# Cpcis_connectors_P1_P2_P3.net
KiCad netlist of a schematic drawn in Altium Designer
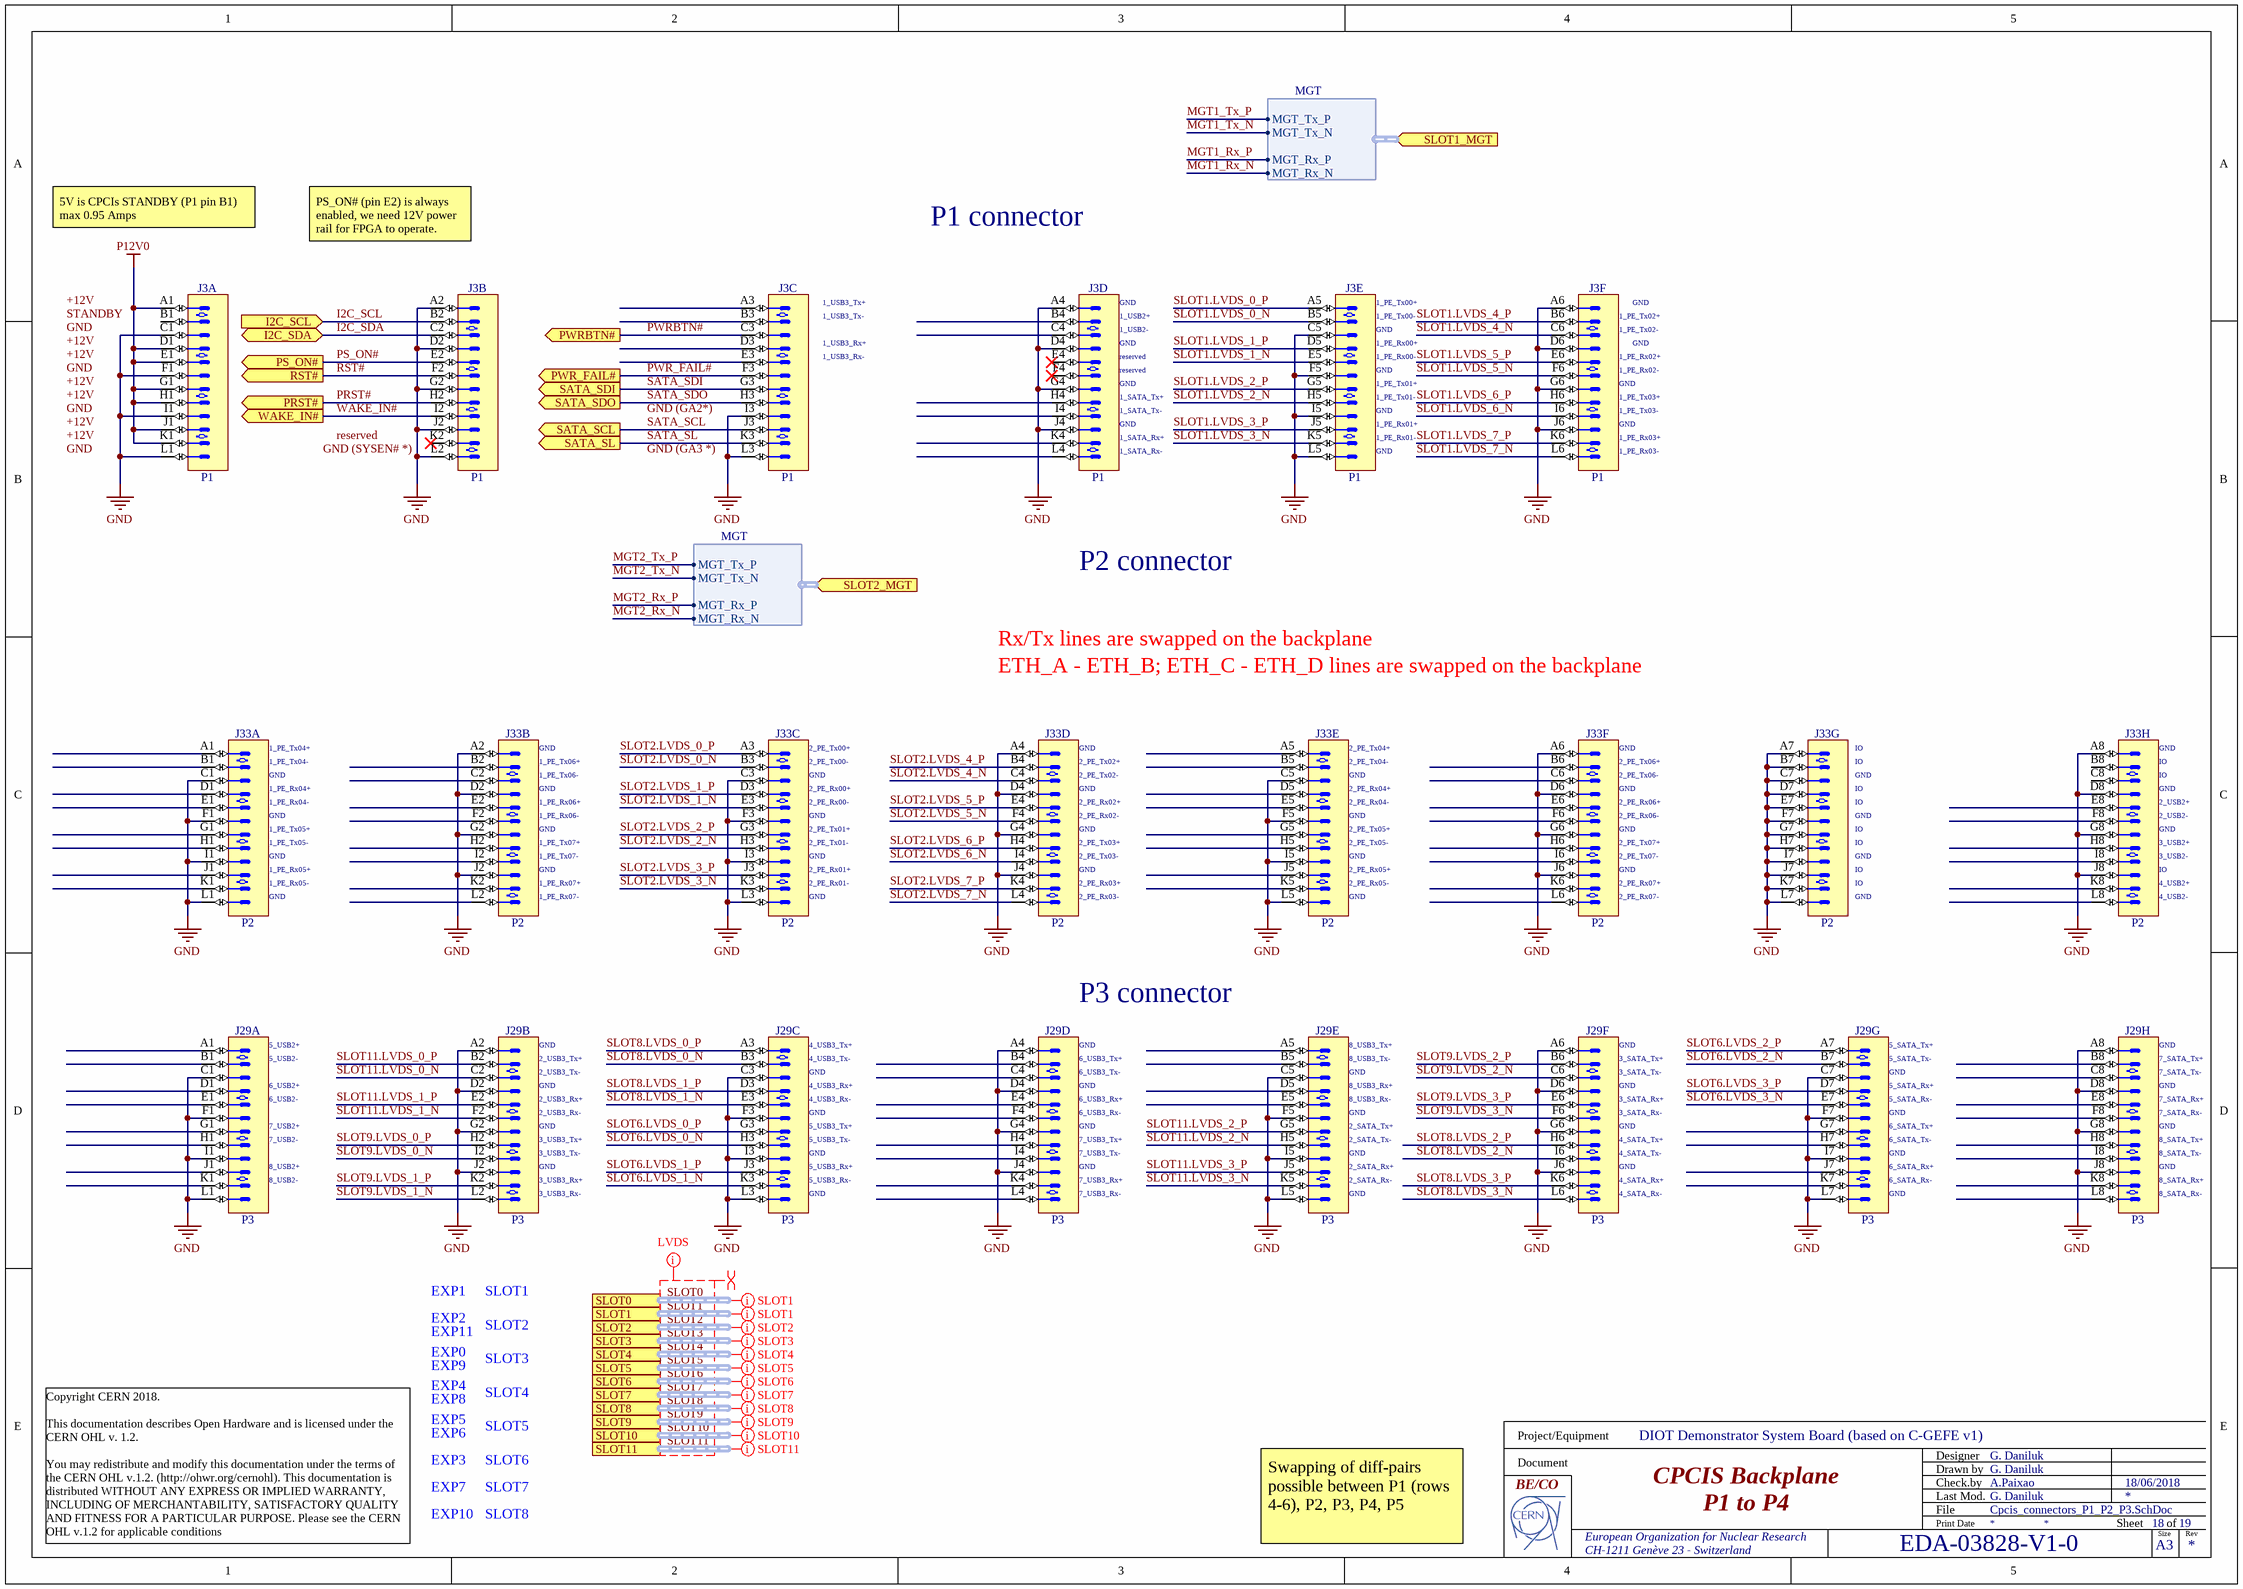
[diagram p0: Cpcis_connectors_P1_P2_P3.SchDoc]

(export (version "E")
  (design (tool "Eeschema 10.0.6"))
  (components
    (comp (ref "J3")
      (value "P1")
      (footprint "AMPHENOL_10052825-101LF")
      (description "72 Contacts Header, 6 Columns, 4 Pairs per Column")
      (fields
        (field (name "PART NUMBER") "AMPHENOL_10052825-101LF")
        (field (name "MANUFACTURER") "AMPHENOL")
        (field (name "AUTHOR") "CERN DEM MR")
      )
      (libsource (lib "Connectors") (part "AMPHENOL_10052825-101LF"))
    )
    (comp (ref "J29")
      (value "P3")
      (footprint "AMPHENOL_10052837-101LF")
      (description "96 Contacts Header, 8 Columns, 4 Pairs per Column")
      (fields
        (field (name "PART NUMBER") "AMPHENOL_10052837-101LF")
        (field (name "MANUFACTURER") "AMPHENOL")
        (field (name "AUTHOR") "CERN DEM MR")
      )
      (libsource (lib "Connectors") (part "AMPHENOL_10052837-101LF"))
    )
    (comp (ref "J33")
      (value "P2")
      (footprint "AMPHENOL_10052837-101LF")
      (description "96 Contacts Header, 8 Columns, 4 Pairs per Column")
      (fields
        (field (name "PART NUMBER") "AMPHENOL_10052837-101LF")
        (field (name "MANUFACTURER") "AMPHENOL")
        (field (name "AUTHOR") "CERN DEM MR")
      )
      (libsource (lib "Connectors") (part "AMPHENOL_10052837-101LF"))
    )
  )
  (nets
    (net (code "18") (name "/I2C_SCL") (class "Default")
      (node (ref "J3") (pin "B2") (pinfunction "B2_B2") (pintype "bidirectional"))
    )
    (net (code "19") (name "/I2C_SDA") (class "Default")
      (node (ref "J3") (pin "C2") (pinfunction "C2_C2") (pintype "bidirectional"))
    )
    (net (code "28") (name "/PRST#") (class "Default")
      (node (ref "J3") (pin "H2") (pinfunction "H2_H2") (pintype "bidirectional"))
    )
    (net (code "29") (name "/PS_ON#") (class "Default")
      (node (ref "J3") (pin "E2") (pinfunction "E2_E2") (pintype "bidirectional"))
    )
    (net (code "30") (name "/PWRBTN#") (class "Default")
      (node (ref "J3") (pin "C3") (pinfunction "C3_C3") (pintype "bidirectional"))
    )
    (net (code "31") (name "/PWR_FAIL#") (class "Default")
      (node (ref "J3") (pin "F3") (pinfunction "F3_F3") (pintype "bidirectional"))
    )
    (net (code "32") (name "/RST#") (class "Default")
      (node (ref "J3") (pin "F2") (pinfunction "F2_F2") (pintype "bidirectional"))
    )
    (net (code "33") (name "/SATA_SCL") (class "Default")
      (node (ref "J3") (pin "J3") (pinfunction "J3_J3") (pintype "bidirectional"))
    )
    (net (code "34") (name "/SATA_SDI") (class "Default")
      (node (ref "J3") (pin "G3") (pinfunction "G3_G3") (pintype "bidirectional"))
    )
    (net (code "35") (name "/SATA_SDO") (class "Default")
      (node (ref "J3") (pin "H3") (pinfunction "H3_H3") (pintype "bidirectional"))
    )
    (net (code "36") (name "/SATA_SL") (class "Default")
      (node (ref "J3") (pin "K3") (pinfunction "K3_K3") (pintype "bidirectional"))
    )
    (net (code "37") (name "/SLOT1.LVDS_0_N") (class "Default")
      (node (ref "J3") (pin "B5") (pinfunction "B5_B5") (pintype "bidirectional"))
    )
    (net (code "38") (name "/SLOT1.LVDS_0_P") (class "Default")
      (node (ref "J3") (pin "A5") (pinfunction "A5_A5") (pintype "bidirectional"))
    )
    (net (code "39") (name "/SLOT1.LVDS_1_N") (class "Default")
      (node (ref "J3") (pin "E5") (pinfunction "E5_E5") (pintype "bidirectional"))
    )
    (net (code "40") (name "/SLOT1.LVDS_1_P") (class "Default")
      (node (ref "J3") (pin "D5") (pinfunction "D5_D5") (pintype "bidirectional"))
    )
    (net (code "41") (name "/SLOT1.LVDS_2_N") (class "Default")
      (node (ref "J3") (pin "H5") (pinfunction "H5_H5") (pintype "bidirectional"))
    )
    (net (code "42") (name "/SLOT1.LVDS_2_P") (class "Default")
      (node (ref "J3") (pin "G5") (pinfunction "G5_G5") (pintype "bidirectional"))
    )
    (net (code "43") (name "/SLOT1.LVDS_3_N") (class "Default")
      (node (ref "J3") (pin "K5") (pinfunction "K5_K5") (pintype "bidirectional"))
    )
    (net (code "44") (name "/SLOT1.LVDS_3_P") (class "Default")
      (node (ref "J3") (pin "J5") (pinfunction "J5_J5") (pintype "bidirectional"))
    )
    (net (code "45") (name "/SLOT1.LVDS_4_N") (class "Default")
      (node (ref "J3") (pin "C6") (pinfunction "C6_C6") (pintype "bidirectional"))
    )
    (net (code "46") (name "/SLOT1.LVDS_4_P") (class "Default")
      (node (ref "J3") (pin "B6") (pinfunction "B6_B6") (pintype "bidirectional"))
    )
    (net (code "47") (name "/SLOT1.LVDS_5_N") (class "Default")
      (node (ref "J3") (pin "F6") (pinfunction "F6_F6") (pintype "bidirectional"))
    )
    (net (code "48") (name "/SLOT1.LVDS_5_P") (class "Default")
      (node (ref "J3") (pin "E6") (pinfunction "E6_E6") (pintype "bidirectional"))
    )
    (net (code "49") (name "/SLOT1.LVDS_6_N") (class "Default")
      (node (ref "J3") (pin "I6") (pinfunction "I6_I6") (pintype "bidirectional"))
    )
    (net (code "50") (name "/SLOT1.LVDS_6_P") (class "Default")
      (node (ref "J3") (pin "H6") (pinfunction "H6_H6") (pintype "bidirectional"))
    )
    (net (code "51") (name "/SLOT1.LVDS_7_N") (class "Default")
      (node (ref "J3") (pin "L6") (pinfunction "L6_L6") (pintype "bidirectional"))
    )
    (net (code "52") (name "/SLOT1.LVDS_7_P") (class "Default")
      (node (ref "J3") (pin "K6") (pinfunction "K6_K6") (pintype "bidirectional"))
    )
    (net (code "53") (name "/SLOT2.LVDS_0_N") (class "Default")
      (node (ref "J33") (pin "B3") (pinfunction "B3_B3") (pintype "bidirectional"))
    )
    (net (code "54") (name "/SLOT2.LVDS_0_P") (class "Default")
      (node (ref "J33") (pin "A3") (pinfunction "A3_A3") (pintype "bidirectional"))
    )
    (net (code "55") (name "/SLOT2.LVDS_1_N") (class "Default")
      (node (ref "J33") (pin "E3") (pinfunction "E3_E3") (pintype "bidirectional"))
    )
    (net (code "56") (name "/SLOT2.LVDS_1_P") (class "Default")
      (node (ref "J33") (pin "D3") (pinfunction "D3_D3") (pintype "bidirectional"))
    )
    (net (code "57") (name "/SLOT2.LVDS_2_N") (class "Default")
      (node (ref "J33") (pin "H3") (pinfunction "H3_H3") (pintype "bidirectional"))
    )
    (net (code "58") (name "/SLOT2.LVDS_2_P") (class "Default")
      (node (ref "J33") (pin "G3") (pinfunction "G3_G3") (pintype "bidirectional"))
    )
    (net (code "59") (name "/SLOT2.LVDS_3_N") (class "Default")
      (node (ref "J33") (pin "K3") (pinfunction "K3_K3") (pintype "bidirectional"))
    )
    (net (code "60") (name "/SLOT2.LVDS_3_P") (class "Default")
      (node (ref "J33") (pin "J3") (pinfunction "J3_J3") (pintype "bidirectional"))
    )
    (net (code "61") (name "/SLOT2.LVDS_4_N") (class "Default")
      (node (ref "J33") (pin "C4") (pinfunction "C4_C4") (pintype "bidirectional"))
    )
    (net (code "62") (name "/SLOT2.LVDS_4_P") (class "Default")
      (node (ref "J33") (pin "B4") (pinfunction "B4_B4") (pintype "bidirectional"))
    )
    (net (code "63") (name "/SLOT2.LVDS_5_N") (class "Default")
      (node (ref "J33") (pin "F4") (pinfunction "F4_F4") (pintype "bidirectional"))
    )
    (net (code "64") (name "/SLOT2.LVDS_5_P") (class "Default")
      (node (ref "J33") (pin "E4") (pinfunction "E4_E4") (pintype "bidirectional"))
    )
    (net (code "65") (name "/SLOT2.LVDS_6_N") (class "Default")
      (node (ref "J33") (pin "I4") (pinfunction "I4_I4") (pintype "bidirectional"))
    )
    (net (code "66") (name "/SLOT2.LVDS_6_P") (class "Default")
      (node (ref "J33") (pin "H4") (pinfunction "H4_H4") (pintype "bidirectional"))
    )
    (net (code "67") (name "/SLOT2.LVDS_7_N") (class "Default")
      (node (ref "J33") (pin "L4") (pinfunction "L4_L4") (pintype "bidirectional"))
    )
    (net (code "68") (name "/SLOT2.LVDS_7_P") (class "Default")
      (node (ref "J33") (pin "K4") (pinfunction "K4_K4") (pintype "bidirectional"))
    )
    (net (code "69") (name "/SLOT6.LVDS_0_N") (class "Default")
      (node (ref "J29") (pin "H3") (pinfunction "H3_H3") (pintype "bidirectional"))
    )
    (net (code "70") (name "/SLOT6.LVDS_0_P") (class "Default")
      (node (ref "J29") (pin "G3") (pinfunction "G3_G3") (pintype "bidirectional"))
    )
    (net (code "71") (name "/SLOT6.LVDS_1_N") (class "Default")
      (node (ref "J29") (pin "K3") (pinfunction "K3_K3") (pintype "bidirectional"))
    )
    (net (code "72") (name "/SLOT6.LVDS_1_P") (class "Default")
      (node (ref "J29") (pin "J3") (pinfunction "J3_J3") (pintype "bidirectional"))
    )
    (net (code "73") (name "/SLOT6.LVDS_2_N") (class "Default")
      (node (ref "J29") (pin "B7") (pinfunction "B7_B7") (pintype "bidirectional"))
    )
    (net (code "74") (name "/SLOT6.LVDS_2_P") (class "Default")
      (node (ref "J29") (pin "A7") (pinfunction "A7_A7") (pintype "bidirectional"))
    )
    (net (code "75") (name "/SLOT6.LVDS_3_N") (class "Default")
      (node (ref "J29") (pin "E7") (pinfunction "E7_E7") (pintype "bidirectional"))
    )
    (net (code "76") (name "/SLOT6.LVDS_3_P") (class "Default")
      (node (ref "J29") (pin "D7") (pinfunction "D7_D7") (pintype "bidirectional"))
    )
    (net (code "77") (name "/SLOT8.LVDS_0_N") (class "Default")
      (node (ref "J29") (pin "B3") (pinfunction "B3_B3") (pintype "bidirectional"))
    )
    (net (code "78") (name "/SLOT8.LVDS_0_P") (class "Default")
      (node (ref "J29") (pin "A3") (pinfunction "A3_A3") (pintype "bidirectional"))
    )
    (net (code "79") (name "/SLOT8.LVDS_1_N") (class "Default")
      (node (ref "J29") (pin "E3") (pinfunction "E3_E3") (pintype "bidirectional"))
    )
    (net (code "80") (name "/SLOT8.LVDS_1_P") (class "Default")
      (node (ref "J29") (pin "D3") (pinfunction "D3_D3") (pintype "bidirectional"))
    )
    (net (code "81") (name "/SLOT8.LVDS_2_N") (class "Default")
      (node (ref "J29") (pin "I6") (pinfunction "I6_I6") (pintype "bidirectional"))
    )
    (net (code "82") (name "/SLOT8.LVDS_2_P") (class "Default")
      (node (ref "J29") (pin "H6") (pinfunction "H6_H6") (pintype "bidirectional"))
    )
    (net (code "83") (name "/SLOT8.LVDS_3_N") (class "Default")
      (node (ref "J29") (pin "L6") (pinfunction "L6_L6") (pintype "bidirectional"))
    )
    (net (code "84") (name "/SLOT8.LVDS_3_P") (class "Default")
      (node (ref "J29") (pin "K6") (pinfunction "K6_K6") (pintype "bidirectional"))
    )
    (net (code "85") (name "/SLOT9.LVDS_0_N") (class "Default")
      (node (ref "J29") (pin "I2") (pinfunction "I2_I2") (pintype "bidirectional"))
    )
    (net (code "86") (name "/SLOT9.LVDS_0_P") (class "Default")
      (node (ref "J29") (pin "H2") (pinfunction "H2_H2") (pintype "bidirectional"))
    )
    (net (code "87") (name "/SLOT9.LVDS_1_N") (class "Default")
      (node (ref "J29") (pin "L2") (pinfunction "L2_L2") (pintype "bidirectional"))
    )
    (net (code "88") (name "/SLOT9.LVDS_1_P") (class "Default")
      (node (ref "J29") (pin "K2") (pinfunction "K2_K2") (pintype "bidirectional"))
    )
    (net (code "89") (name "/SLOT9.LVDS_2_N") (class "Default")
      (node (ref "J29") (pin "C6") (pinfunction "C6_C6") (pintype "bidirectional"))
    )
    (net (code "90") (name "/SLOT9.LVDS_2_P") (class "Default")
      (node (ref "J29") (pin "B6") (pinfunction "B6_B6") (pintype "bidirectional"))
    )
    (net (code "91") (name "/SLOT9.LVDS_3_N") (class "Default")
      (node (ref "J29") (pin "F6") (pinfunction "F6_F6") (pintype "bidirectional"))
    )
    (net (code "92") (name "/SLOT9.LVDS_3_P") (class "Default")
      (node (ref "J29") (pin "E6") (pinfunction "E6_E6") (pintype "bidirectional"))
    )
    (net (code "93") (name "/SLOT11.LVDS_0_N") (class "Default")
      (node (ref "J29") (pin "C2") (pinfunction "C2_C2") (pintype "bidirectional"))
    )
    (net (code "94") (name "/SLOT11.LVDS_0_P") (class "Default")
      (node (ref "J29") (pin "B2") (pinfunction "B2_B2") (pintype "bidirectional"))
    )
    (net (code "95") (name "/SLOT11.LVDS_1_N") (class "Default")
      (node (ref "J29") (pin "F2") (pinfunction "F2_F2") (pintype "bidirectional"))
    )
    (net (code "96") (name "/SLOT11.LVDS_1_P") (class "Default")
      (node (ref "J29") (pin "E2") (pinfunction "E2_E2") (pintype "bidirectional"))
    )
    (net (code "97") (name "/SLOT11.LVDS_2_N") (class "Default")
      (node (ref "J29") (pin "H5") (pinfunction "H5_H5") (pintype "bidirectional"))
    )
    (net (code "98") (name "/SLOT11.LVDS_2_P") (class "Default")
      (node (ref "J29") (pin "G5") (pinfunction "G5_G5") (pintype "bidirectional"))
    )
    (net (code "99") (name "/SLOT11.LVDS_3_N") (class "Default")
      (node (ref "J29") (pin "K5") (pinfunction "K5_K5") (pintype "bidirectional"))
    )
    (net (code "100") (name "/SLOT11.LVDS_3_P") (class "Default")
      (node (ref "J29") (pin "J5") (pinfunction "J5_J5") (pintype "bidirectional"))
    )
    (net (code "102") (name "/WAKE_IN#") (class "Default")
      (node (ref "J3") (pin "I2") (pinfunction "I2_I2") (pintype "bidirectional"))
    )
    (net (code "117") (name "GND") (class "Default")
      (node (ref "J29") (pin "A2") (pinfunction "A2_A2") (pintype "bidirectional"))
      (node (ref "J29") (pin "A4") (pinfunction "A4_A4") (pintype "bidirectional"))
      (node (ref "J29") (pin "A6") (pinfunction "A6_A6") (pintype "bidirectional"))
      (node (ref "J29") (pin "A8") (pinfunction "A8_A8") (pintype "bidirectional"))
      (node (ref "J29") (pin "C1") (pinfunction "C1_C1") (pintype "bidirectional"))
      (node (ref "J29") (pin "C3") (pinfunction "C3_C3") (pintype "bidirectional"))
      (node (ref "J29") (pin "C5") (pinfunction "C5_C5") (pintype "bidirectional"))
      (node (ref "J29") (pin "C7") (pinfunction "C7_C7") (pintype "bidirectional"))
      (node (ref "J29") (pin "D2") (pinfunction "D2_D2") (pintype "bidirectional"))
      (node (ref "J29") (pin "D4") (pinfunction "D4_D4") (pintype "bidirectional"))
      (node (ref "J29") (pin "D6") (pinfunction "D6_D6") (pintype "bidirectional"))
      (node (ref "J29") (pin "D8") (pinfunction "D8_D8") (pintype "bidirectional"))
      (node (ref "J29") (pin "F1") (pinfunction "F1_F1") (pintype "bidirectional"))
      (node (ref "J29") (pin "F3") (pinfunction "F3_F3") (pintype "bidirectional"))
      (node (ref "J29") (pin "F5") (pinfunction "F5_F5") (pintype "bidirectional"))
      (node (ref "J29") (pin "F7") (pinfunction "F7_F7") (pintype "bidirectional"))
      (node (ref "J29") (pin "G2") (pinfunction "G2_G2") (pintype "bidirectional"))
      (node (ref "J29") (pin "G4") (pinfunction "G4_G4") (pintype "bidirectional"))
      (node (ref "J29") (pin "G6") (pinfunction "G6_G6") (pintype "bidirectional"))
      (node (ref "J29") (pin "G8") (pinfunction "G8_G8") (pintype "bidirectional"))
      (node (ref "J29") (pin "I1") (pinfunction "I1_I1") (pintype "bidirectional"))
      (node (ref "J29") (pin "I3") (pinfunction "I3_I3") (pintype "bidirectional"))
      (node (ref "J29") (pin "I5") (pinfunction "I5_I5") (pintype "bidirectional"))
      (node (ref "J29") (pin "I7") (pinfunction "I7_I7") (pintype "bidirectional"))
      (node (ref "J29") (pin "J2") (pinfunction "J2_J2") (pintype "bidirectional"))
      (node (ref "J29") (pin "J4") (pinfunction "J4_J4") (pintype "bidirectional"))
      (node (ref "J29") (pin "J6") (pinfunction "J6_J6") (pintype "bidirectional"))
      (node (ref "J29") (pin "J8") (pinfunction "J8_J8") (pintype "bidirectional"))
      (node (ref "J29") (pin "L1") (pinfunction "L1_L1") (pintype "bidirectional"))
      (node (ref "J29") (pin "L3") (pinfunction "L3_L3") (pintype "bidirectional"))
      (node (ref "J29") (pin "L5") (pinfunction "L5_L5") (pintype "bidirectional"))
      (node (ref "J29") (pin "L7") (pinfunction "L7_L7") (pintype "bidirectional"))
      (node (ref "J3") (pin "A2") (pinfunction "A2_A2") (pintype "bidirectional"))
      (node (ref "J3") (pin "A4") (pinfunction "A4_A4") (pintype "bidirectional"))
      (node (ref "J3") (pin "A6") (pinfunction "A6_A6") (pintype "bidirectional"))
      (node (ref "J3") (pin "C1") (pinfunction "C1_C1") (pintype "bidirectional"))
      (node (ref "J3") (pin "C5") (pinfunction "C5_C5") (pintype "bidirectional"))
      (node (ref "J3") (pin "D2") (pinfunction "D2_D2") (pintype "bidirectional"))
      (node (ref "J3") (pin "D4") (pinfunction "D4_D4") (pintype "bidirectional"))
      (node (ref "J3") (pin "D6") (pinfunction "D6_D6") (pintype "bidirectional"))
      (node (ref "J3") (pin "F1") (pinfunction "F1_F1") (pintype "bidirectional"))
      (node (ref "J3") (pin "F5") (pinfunction "F5_F5") (pintype "bidirectional"))
      (node (ref "J3") (pin "G2") (pinfunction "G2_G2") (pintype "bidirectional"))
      (node (ref "J3") (pin "G4") (pinfunction "G4_G4") (pintype "bidirectional"))
      (node (ref "J3") (pin "G6") (pinfunction "G6_G6") (pintype "bidirectional"))
      (node (ref "J3") (pin "I1") (pinfunction "I1_I1") (pintype "bidirectional"))
      (node (ref "J3") (pin "I3") (pinfunction "I3_I3") (pintype "bidirectional"))
      (node (ref "J3") (pin "I5") (pinfunction "I5_I5") (pintype "bidirectional"))
      (node (ref "J3") (pin "J2") (pinfunction "J2_J2") (pintype "bidirectional"))
      (node (ref "J3") (pin "J4") (pinfunction "J4_J4") (pintype "bidirectional"))
      (node (ref "J3") (pin "J6") (pinfunction "J6_J6") (pintype "bidirectional"))
      (node (ref "J3") (pin "L1") (pinfunction "L1_L1") (pintype "bidirectional"))
      (node (ref "J3") (pin "L2") (pinfunction "L2_L2") (pintype "bidirectional"))
      (node (ref "J3") (pin "L3") (pinfunction "L3_L3") (pintype "bidirectional"))
      (node (ref "J3") (pin "L5") (pinfunction "L5_L5") (pintype "bidirectional"))
      (node (ref "J33") (pin "A2") (pinfunction "A2_A2") (pintype "bidirectional"))
      (node (ref "J33") (pin "A4") (pinfunction "A4_A4") (pintype "bidirectional"))
      (node (ref "J33") (pin "A6") (pinfunction "A6_A6") (pintype "bidirectional"))
      (node (ref "J33") (pin "A7") (pinfunction "A7_A7") (pintype "bidirectional"))
      (node (ref "J33") (pin "A8") (pinfunction "A8_A8") (pintype "bidirectional"))
      (node (ref "J33") (pin "B7") (pinfunction "B7_B7") (pintype "bidirectional"))
      (node (ref "J33") (pin "C1") (pinfunction "C1_C1") (pintype "bidirectional"))
      (node (ref "J33") (pin "C3") (pinfunction "C3_C3") (pintype "bidirectional"))
      (node (ref "J33") (pin "C5") (pinfunction "C5_C5") (pintype "bidirectional"))
      (node (ref "J33") (pin "C7") (pinfunction "C7_C7") (pintype "bidirectional"))
      (node (ref "J33") (pin "D2") (pinfunction "D2_D2") (pintype "bidirectional"))
      (node (ref "J33") (pin "D4") (pinfunction "D4_D4") (pintype "bidirectional"))
      (node (ref "J33") (pin "D6") (pinfunction "D6_D6") (pintype "bidirectional"))
      (node (ref "J33") (pin "D7") (pinfunction "D7_D7") (pintype "bidirectional"))
      (node (ref "J33") (pin "D8") (pinfunction "D8_D8") (pintype "bidirectional"))
      (node (ref "J33") (pin "E7") (pinfunction "E7_E7") (pintype "bidirectional"))
      (node (ref "J33") (pin "F1") (pinfunction "F1_F1") (pintype "bidirectional"))
      (node (ref "J33") (pin "F3") (pinfunction "F3_F3") (pintype "bidirectional"))
      (node (ref "J33") (pin "F5") (pinfunction "F5_F5") (pintype "bidirectional"))
      (node (ref "J33") (pin "F7") (pinfunction "F7_F7") (pintype "bidirectional"))
      (node (ref "J33") (pin "G2") (pinfunction "G2_G2") (pintype "bidirectional"))
      (node (ref "J33") (pin "G4") (pinfunction "G4_G4") (pintype "bidirectional"))
      (node (ref "J33") (pin "G6") (pinfunction "G6_G6") (pintype "bidirectional"))
      (node (ref "J33") (pin "G7") (pinfunction "G7_G7") (pintype "bidirectional"))
      (node (ref "J33") (pin "G8") (pinfunction "G8_G8") (pintype "bidirectional"))
      (node (ref "J33") (pin "H7") (pinfunction "H7_H7") (pintype "bidirectional"))
      (node (ref "J33") (pin "I1") (pinfunction "I1_I1") (pintype "bidirectional"))
      (node (ref "J33") (pin "I3") (pinfunction "I3_I3") (pintype "bidirectional"))
      (node (ref "J33") (pin "I5") (pinfunction "I5_I5") (pintype "bidirectional"))
      (node (ref "J33") (pin "I7") (pinfunction "I7_I7") (pintype "bidirectional"))
      (node (ref "J33") (pin "J2") (pinfunction "J2_J2") (pintype "bidirectional"))
      (node (ref "J33") (pin "J4") (pinfunction "J4_J4") (pintype "bidirectional"))
      (node (ref "J33") (pin "J6") (pinfunction "J6_J6") (pintype "bidirectional"))
      (node (ref "J33") (pin "J7") (pinfunction "J7_J7") (pintype "bidirectional"))
      (node (ref "J33") (pin "J8") (pinfunction "J8_J8") (pintype "bidirectional"))
      (node (ref "J33") (pin "K7") (pinfunction "K7_K7") (pintype "bidirectional"))
      (node (ref "J33") (pin "L1") (pinfunction "L1_L1") (pintype "bidirectional"))
      (node (ref "J33") (pin "L3") (pinfunction "L3_L3") (pintype "bidirectional"))
      (node (ref "J33") (pin "L5") (pinfunction "L5_L5") (pintype "bidirectional"))
      (node (ref "J33") (pin "L7") (pinfunction "L7_L7") (pintype "bidirectional"))
    )
    (net (code "118") (name "P12V0") (class "Default")
      (node (ref "J3") (pin "A1") (pinfunction "A1_A1") (pintype "bidirectional"))
      (node (ref "J3") (pin "D1") (pinfunction "D1_D1") (pintype "bidirectional"))
      (node (ref "J3") (pin "E1") (pinfunction "E1_E1") (pintype "bidirectional"))
      (node (ref "J3") (pin "G1") (pinfunction "G1_G1") (pintype "bidirectional"))
      (node (ref "J3") (pin "H1") (pinfunction "H1_H1") (pintype "bidirectional"))
      (node (ref "J3") (pin "J1") (pinfunction "J1_J1") (pintype "bidirectional"))
      (node (ref "J3") (pin "K1") (pinfunction "K1_K1") (pintype "bidirectional"))
    )
    (net (code "119") (name "unconnected-(J3-PadA3)") (class "Default")
      (node (ref "J3") (pin "A3") (pinfunction "A3_A3") (pintype "bidirectional"))
    )
    (net (code "120") (name "unconnected-(J3-PadB1)") (class "Default")
      (node (ref "J3") (pin "B1") (pinfunction "B1_B1") (pintype "bidirectional"))
    )
    (net (code "121") (name "unconnected-(J3-PadB3)") (class "Default")
      (node (ref "J3") (pin "B3") (pinfunction "B3_B3") (pintype "bidirectional"))
    )
    (net (code "122") (name "unconnected-(J3-PadB4)") (class "Default")
      (node (ref "J3") (pin "B4") (pinfunction "B4_B4") (pintype "bidirectional"))
    )
    (net (code "123") (name "unconnected-(J3-PadC4)") (class "Default")
      (node (ref "J3") (pin "C4") (pinfunction "C4_C4") (pintype "bidirectional"))
    )
    (net (code "124") (name "unconnected-(J3-PadD3)") (class "Default")
      (node (ref "J3") (pin "D3") (pinfunction "D3_D3") (pintype "bidirectional"))
    )
    (net (code "125") (name "unconnected-(J3-PadE3)") (class "Default")
      (node (ref "J3") (pin "E3") (pinfunction "E3_E3") (pintype "bidirectional"))
    )
    (net (code "126") (name "unconnected-(J3-PadE4)") (class "Default")
      (node (ref "J3") (pin "E4") (pinfunction "E4_E4") (pintype "bidirectional+no_connect"))
    )
    (net (code "127") (name "unconnected-(J3-PadF4)") (class "Default")
      (node (ref "J3") (pin "F4") (pinfunction "F4_F4") (pintype "bidirectional+no_connect"))
    )
    (net (code "128") (name "unconnected-(J3-PadH4)") (class "Default")
      (node (ref "J3") (pin "H4") (pinfunction "H4_H4") (pintype "bidirectional"))
    )
    (net (code "129") (name "unconnected-(J3-PadI4)") (class "Default")
      (node (ref "J3") (pin "I4") (pinfunction "I4_I4") (pintype "bidirectional"))
    )
    (net (code "130") (name "unconnected-(J3-PadK2)") (class "Default")
      (node (ref "J3") (pin "K2") (pinfunction "K2_K2") (pintype "bidirectional+no_connect"))
    )
    (net (code "131") (name "unconnected-(J3-PadK4)") (class "Default")
      (node (ref "J3") (pin "K4") (pinfunction "K4_K4") (pintype "bidirectional"))
    )
    (net (code "132") (name "unconnected-(J3-PadL4)") (class "Default")
      (node (ref "J3") (pin "L4") (pinfunction "L4_L4") (pintype "bidirectional"))
    )
    (net (code "133") (name "unconnected-(J29-PadA1)") (class "Default")
      (node (ref "J29") (pin "A1") (pinfunction "A1_A1") (pintype "bidirectional"))
    )
    (net (code "134") (name "unconnected-(J29-PadA5)") (class "Default")
      (node (ref "J29") (pin "A5") (pinfunction "A5_A5") (pintype "bidirectional"))
    )
    (net (code "135") (name "unconnected-(J29-PadB1)") (class "Default")
      (node (ref "J29") (pin "B1") (pinfunction "B1_B1") (pintype "bidirectional"))
    )
    (net (code "136") (name "unconnected-(J29-PadB4)") (class "Default")
      (node (ref "J29") (pin "B4") (pinfunction "B4_B4") (pintype "bidirectional"))
    )
    (net (code "137") (name "unconnected-(J29-PadB5)") (class "Default")
      (node (ref "J29") (pin "B5") (pinfunction "B5_B5") (pintype "bidirectional"))
    )
    (net (code "138") (name "unconnected-(J29-PadB8)") (class "Default")
      (node (ref "J29") (pin "B8") (pinfunction "B8_B8") (pintype "bidirectional"))
    )
    (net (code "139") (name "unconnected-(J29-PadC4)") (class "Default")
      (node (ref "J29") (pin "C4") (pinfunction "C4_C4") (pintype "bidirectional"))
    )
    (net (code "140") (name "unconnected-(J29-PadC8)") (class "Default")
      (node (ref "J29") (pin "C8") (pinfunction "C8_C8") (pintype "bidirectional"))
    )
    (net (code "141") (name "unconnected-(J29-PadD1)") (class "Default")
      (node (ref "J29") (pin "D1") (pinfunction "D1_D1") (pintype "bidirectional"))
    )
    (net (code "142") (name "unconnected-(J29-PadD5)") (class "Default")
      (node (ref "J29") (pin "D5") (pinfunction "D5_D5") (pintype "bidirectional"))
    )
    (net (code "143") (name "unconnected-(J29-PadE1)") (class "Default")
      (node (ref "J29") (pin "E1") (pinfunction "E1_E1") (pintype "bidirectional"))
    )
    (net (code "144") (name "unconnected-(J29-PadE4)") (class "Default")
      (node (ref "J29") (pin "E4") (pinfunction "E4_E4") (pintype "bidirectional"))
    )
    (net (code "145") (name "unconnected-(J29-PadE5)") (class "Default")
      (node (ref "J29") (pin "E5") (pinfunction "E5_E5") (pintype "bidirectional"))
    )
    (net (code "146") (name "unconnected-(J29-PadE8)") (class "Default")
      (node (ref "J29") (pin "E8") (pinfunction "E8_E8") (pintype "bidirectional"))
    )
    (net (code "147") (name "unconnected-(J29-PadF4)") (class "Default")
      (node (ref "J29") (pin "F4") (pinfunction "F4_F4") (pintype "bidirectional"))
    )
    (net (code "148") (name "unconnected-(J29-PadF8)") (class "Default")
      (node (ref "J29") (pin "F8") (pinfunction "F8_F8") (pintype "bidirectional"))
    )
    (net (code "149") (name "unconnected-(J29-PadG1)") (class "Default")
      (node (ref "J29") (pin "G1") (pinfunction "G1_G1") (pintype "bidirectional"))
    )
    (net (code "150") (name "unconnected-(J29-PadG7)") (class "Default")
      (node (ref "J29") (pin "G7") (pinfunction "G7_G7") (pintype "bidirectional"))
    )
    (net (code "151") (name "unconnected-(J29-PadH1)") (class "Default")
      (node (ref "J29") (pin "H1") (pinfunction "H1_H1") (pintype "bidirectional"))
    )
    (net (code "152") (name "unconnected-(J29-PadH4)") (class "Default")
      (node (ref "J29") (pin "H4") (pinfunction "H4_H4") (pintype "bidirectional"))
    )
    (net (code "153") (name "unconnected-(J29-PadH7)") (class "Default")
      (node (ref "J29") (pin "H7") (pinfunction "H7_H7") (pintype "bidirectional"))
    )
    (net (code "154") (name "unconnected-(J29-PadH8)") (class "Default")
      (node (ref "J29") (pin "H8") (pinfunction "H8_H8") (pintype "bidirectional"))
    )
    (net (code "155") (name "unconnected-(J29-PadI4)") (class "Default")
      (node (ref "J29") (pin "I4") (pinfunction "I4_I4") (pintype "bidirectional"))
    )
    (net (code "156") (name "unconnected-(J29-PadI8)") (class "Default")
      (node (ref "J29") (pin "I8") (pinfunction "I8_I8") (pintype "bidirectional"))
    )
    (net (code "157") (name "unconnected-(J29-PadJ1)") (class "Default")
      (node (ref "J29") (pin "J1") (pinfunction "J1_J1") (pintype "bidirectional"))
    )
    (net (code "158") (name "unconnected-(J29-PadJ7)") (class "Default")
      (node (ref "J29") (pin "J7") (pinfunction "J7_J7") (pintype "bidirectional"))
    )
    (net (code "159") (name "unconnected-(J29-PadK1)") (class "Default")
      (node (ref "J29") (pin "K1") (pinfunction "K1_K1") (pintype "bidirectional"))
    )
    (net (code "160") (name "unconnected-(J29-PadK4)") (class "Default")
      (node (ref "J29") (pin "K4") (pinfunction "K4_K4") (pintype "bidirectional"))
    )
    (net (code "161") (name "unconnected-(J29-PadK7)") (class "Default")
      (node (ref "J29") (pin "K7") (pinfunction "K7_K7") (pintype "bidirectional"))
    )
    (net (code "162") (name "unconnected-(J29-PadK8)") (class "Default")
      (node (ref "J29") (pin "K8") (pinfunction "K8_K8") (pintype "bidirectional"))
    )
    (net (code "163") (name "unconnected-(J29-PadL4)") (class "Default")
      (node (ref "J29") (pin "L4") (pinfunction "L4_L4") (pintype "bidirectional"))
    )
    (net (code "164") (name "unconnected-(J29-PadL8)") (class "Default")
      (node (ref "J29") (pin "L8") (pinfunction "L8_L8") (pintype "bidirectional"))
    )
    (net (code "165") (name "unconnected-(J33-PadA1)") (class "Default")
      (node (ref "J33") (pin "A1") (pinfunction "A1_A1") (pintype "bidirectional"))
    )
    (net (code "166") (name "unconnected-(J33-PadA5)") (class "Default")
      (node (ref "J33") (pin "A5") (pinfunction "A5_A5") (pintype "bidirectional"))
    )
    (net (code "167") (name "unconnected-(J33-PadB1)") (class "Default")
      (node (ref "J33") (pin "B1") (pinfunction "B1_B1") (pintype "bidirectional"))
    )
    (net (code "168") (name "unconnected-(J33-PadB2)") (class "Default")
      (node (ref "J33") (pin "B2") (pinfunction "B2_B2") (pintype "bidirectional"))
    )
    (net (code "169") (name "unconnected-(J33-PadB5)") (class "Default")
      (node (ref "J33") (pin "B5") (pinfunction "B5_B5") (pintype "bidirectional"))
    )
    (net (code "170") (name "unconnected-(J33-PadB6)") (class "Default")
      (node (ref "J33") (pin "B6") (pinfunction "B6_B6") (pintype "bidirectional"))
    )
    (net (code "171") (name "unconnected-(J33-PadB8)") (class "Default")
      (node (ref "J33") (pin "B8") (pinfunction "B8_B8") (pintype "bidirectional"))
    )
    (net (code "172") (name "unconnected-(J33-PadC2)") (class "Default")
      (node (ref "J33") (pin "C2") (pinfunction "C2_C2") (pintype "bidirectional"))
    )
    (net (code "173") (name "unconnected-(J33-PadC6)") (class "Default")
      (node (ref "J33") (pin "C6") (pinfunction "C6_C6") (pintype "bidirectional"))
    )
    (net (code "174") (name "unconnected-(J33-PadC8)") (class "Default")
      (node (ref "J33") (pin "C8") (pinfunction "C8_C8") (pintype "bidirectional"))
    )
    (net (code "175") (name "unconnected-(J33-PadD1)") (class "Default")
      (node (ref "J33") (pin "D1") (pinfunction "D1_D1") (pintype "bidirectional"))
    )
    (net (code "176") (name "unconnected-(J33-PadD5)") (class "Default")
      (node (ref "J33") (pin "D5") (pinfunction "D5_D5") (pintype "bidirectional"))
    )
    (net (code "177") (name "unconnected-(J33-PadE1)") (class "Default")
      (node (ref "J33") (pin "E1") (pinfunction "E1_E1") (pintype "bidirectional"))
    )
    (net (code "178") (name "unconnected-(J33-PadE2)") (class "Default")
      (node (ref "J33") (pin "E2") (pinfunction "E2_E2") (pintype "bidirectional"))
    )
    (net (code "179") (name "unconnected-(J33-PadE5)") (class "Default")
      (node (ref "J33") (pin "E5") (pinfunction "E5_E5") (pintype "bidirectional"))
    )
    (net (code "180") (name "unconnected-(J33-PadE6)") (class "Default")
      (node (ref "J33") (pin "E6") (pinfunction "E6_E6") (pintype "bidirectional"))
    )
    (net (code "181") (name "unconnected-(J33-PadE8)") (class "Default")
      (node (ref "J33") (pin "E8") (pinfunction "E8_E8") (pintype "bidirectional"))
    )
    (net (code "182") (name "unconnected-(J33-PadF2)") (class "Default")
      (node (ref "J33") (pin "F2") (pinfunction "F2_F2") (pintype "bidirectional"))
    )
    (net (code "183") (name "unconnected-(J33-PadF6)") (class "Default")
      (node (ref "J33") (pin "F6") (pinfunction "F6_F6") (pintype "bidirectional"))
    )
    (net (code "184") (name "unconnected-(J33-PadF8)") (class "Default")
      (node (ref "J33") (pin "F8") (pinfunction "F8_F8") (pintype "bidirectional"))
    )
    (net (code "185") (name "unconnected-(J33-PadG1)") (class "Default")
      (node (ref "J33") (pin "G1") (pinfunction "G1_G1") (pintype "bidirectional"))
    )
    (net (code "186") (name "unconnected-(J33-PadG5)") (class "Default")
      (node (ref "J33") (pin "G5") (pinfunction "G5_G5") (pintype "bidirectional"))
    )
    (net (code "187") (name "unconnected-(J33-PadH1)") (class "Default")
      (node (ref "J33") (pin "H1") (pinfunction "H1_H1") (pintype "bidirectional"))
    )
    (net (code "188") (name "unconnected-(J33-PadH2)") (class "Default")
      (node (ref "J33") (pin "H2") (pinfunction "H2_H2") (pintype "bidirectional"))
    )
    (net (code "189") (name "unconnected-(J33-PadH5)") (class "Default")
      (node (ref "J33") (pin "H5") (pinfunction "H5_H5") (pintype "bidirectional"))
    )
    (net (code "190") (name "unconnected-(J33-PadH6)") (class "Default")
      (node (ref "J33") (pin "H6") (pinfunction "H6_H6") (pintype "bidirectional"))
    )
    (net (code "191") (name "unconnected-(J33-PadH8)") (class "Default")
      (node (ref "J33") (pin "H8") (pinfunction "H8_H8") (pintype "bidirectional"))
    )
    (net (code "192") (name "unconnected-(J33-PadI2)") (class "Default")
      (node (ref "J33") (pin "I2") (pinfunction "I2_I2") (pintype "bidirectional"))
    )
    (net (code "193") (name "unconnected-(J33-PadI6)") (class "Default")
      (node (ref "J33") (pin "I6") (pinfunction "I6_I6") (pintype "bidirectional"))
    )
    (net (code "194") (name "unconnected-(J33-PadI8)") (class "Default")
      (node (ref "J33") (pin "I8") (pinfunction "I8_I8") (pintype "bidirectional"))
    )
    (net (code "195") (name "unconnected-(J33-PadJ1)") (class "Default")
      (node (ref "J33") (pin "J1") (pinfunction "J1_J1") (pintype "bidirectional"))
    )
    (net (code "196") (name "unconnected-(J33-PadJ5)") (class "Default")
      (node (ref "J33") (pin "J5") (pinfunction "J5_J5") (pintype "bidirectional"))
    )
    (net (code "197") (name "unconnected-(J33-PadK1)") (class "Default")
      (node (ref "J33") (pin "K1") (pinfunction "K1_K1") (pintype "bidirectional"))
    )
    (net (code "198") (name "unconnected-(J33-PadK2)") (class "Default")
      (node (ref "J33") (pin "K2") (pinfunction "K2_K2") (pintype "bidirectional"))
    )
    (net (code "199") (name "unconnected-(J33-PadK5)") (class "Default")
      (node (ref "J33") (pin "K5") (pinfunction "K5_K5") (pintype "bidirectional"))
    )
    (net (code "200") (name "unconnected-(J33-PadK6)") (class "Default")
      (node (ref "J33") (pin "K6") (pinfunction "K6_K6") (pintype "bidirectional"))
    )
    (net (code "201") (name "unconnected-(J33-PadK8)") (class "Default")
      (node (ref "J33") (pin "K8") (pinfunction "K8_K8") (pintype "bidirectional"))
    )
    (net (code "202") (name "unconnected-(J33-PadL2)") (class "Default")
      (node (ref "J33") (pin "L2") (pinfunction "L2_L2") (pintype "bidirectional"))
    )
    (net (code "203") (name "unconnected-(J33-PadL6)") (class "Default")
      (node (ref "J33") (pin "L6") (pinfunction "L6_L6") (pintype "bidirectional"))
    )
    (net (code "204") (name "unconnected-(J33-PadL8)") (class "Default")
      (node (ref "J33") (pin "L8") (pinfunction "L8_L8") (pintype "bidirectional"))
    )
  )
)
